# proximity.net
KiCad netlist of a schematic drawn in EAGLE
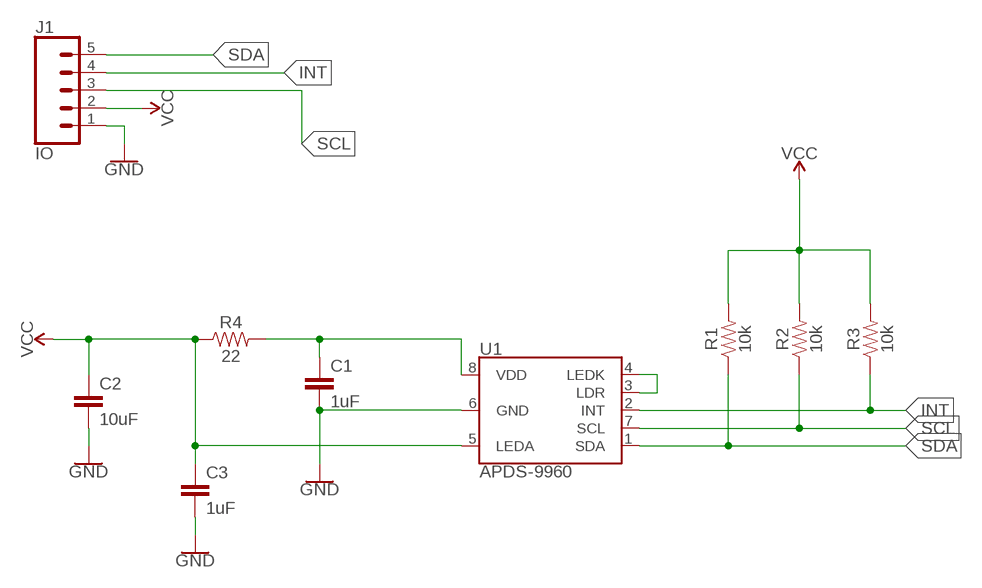
[diagram p0: schematic, sheet 1]

(export (version "E")
  (design (tool "Eeschema 10.0.6"))
  (components
    (comp (ref "C1")
      (value "1uF")
      (footprint "eagle-import:CAP-PTH-SMALL-KIT")
      (libsource (lib "eagle-import") (part "0.1UF-KIT-EZ-50V-20%"))
    )
    (comp (ref "C2")
      (value "10uF")
      (footprint "eagle-import:CAP-PTH-SMALL-KIT")
      (libsource (lib "eagle-import") (part "0.1UF-KIT-EZ-50V-20%"))
    )
    (comp (ref "C3")
      (value "1uF")
      (footprint "eagle-import:CAP-PTH-SMALL-KIT")
      (libsource (lib "eagle-import") (part "0.1UF-KIT-EZ-50V-20%"))
    )
    (comp (ref "J1")
      (value "IO")
      (footprint "eagle-import:1X05")
      (libsource (lib "eagle-import") (part "CONN_05"))
    )
    (comp (ref "R1")
      (value "10k")
      (footprint "eagle-import:AXIAL-0.3")
      (libsource (lib "eagle-import") (part "10KOHM-HORIZ-1/4W-1%"))
    )
    (comp (ref "R2")
      (value "10k")
      (footprint "eagle-import:AXIAL-0.3")
      (libsource (lib "eagle-import") (part "10KOHM-HORIZ-1/4W-1%"))
    )
    (comp (ref "R3")
      (value "10k")
      (footprint "eagle-import:AXIAL-0.3")
      (libsource (lib "eagle-import") (part "10KOHM-HORIZ-1/4W-1%"))
    )
    (comp (ref "R4")
      (value "22")
      (footprint "eagle-import:AXIAL-0.3")
      (libsource (lib "eagle-import") (part "10KOHM-HORIZ-1/4W-1%"))
    )
    (comp (ref "U1")
      (value "APDS-9960")
      (footprint "eagle-import:APDS-9960")
      (libsource (lib "eagle-import") (part "APDS-9960"))
    )
  )
  (nets
    (net (code "1") (name "GND") (class "Default")
      (node (ref "C1") (pin "2") (pinfunction "2_2") (pintype "passive"))
      (node (ref "C2") (pin "2") (pinfunction "2_2") (pintype "passive"))
      (node (ref "C3") (pin "2") (pinfunction "2_2") (pintype "passive"))
      (node (ref "J1") (pin "1") (pinfunction "1_1") (pintype "passive"))
      (node (ref "U1") (pin "6") (pinfunction "GND_6") (pintype "bidirectional"))
    )
    (net (code "2") (name "INT") (class "Default")
      (node (ref "J1") (pin "4") (pinfunction "4_4") (pintype "passive"))
      (node (ref "R3") (pin "P$1") (pinfunction "1_P$1") (pintype "passive"))
      (node (ref "U1") (pin "2") (pinfunction "INT_2") (pintype "bidirectional"))
    )
    (net (code "3") (name "Net-(R4-2)") (class "Default")
      (node (ref "C1") (pin "1") (pinfunction "1_1") (pintype "passive"))
      (node (ref "R4") (pin "P$2") (pinfunction "2_P$2") (pintype "passive"))
      (node (ref "U1") (pin "8") (pinfunction "VDD_8") (pintype "bidirectional"))
    )
    (net (code "4") (name "Net-(U1-LDR)") (class "Default")
      (node (ref "U1") (pin "3") (pinfunction "LDR_3") (pintype "bidirectional"))
      (node (ref "U1") (pin "4") (pinfunction "LEDK_4") (pintype "bidirectional"))
    )
    (net (code "5") (name "SCL") (class "Default")
      (node (ref "J1") (pin "3") (pinfunction "3_3") (pintype "passive"))
      (node (ref "R2") (pin "P$1") (pinfunction "1_P$1") (pintype "passive"))
      (node (ref "U1") (pin "7") (pinfunction "SCL_7") (pintype "bidirectional"))
    )
    (net (code "6") (name "SDA") (class "Default")
      (node (ref "J1") (pin "5") (pinfunction "5_5") (pintype "passive"))
      (node (ref "R1") (pin "P$1") (pinfunction "1_P$1") (pintype "passive"))
      (node (ref "U1") (pin "1") (pinfunction "SDA_1") (pintype "bidirectional"))
    )
    (net (code "7") (name "VCC") (class "Default")
      (node (ref "C2") (pin "1") (pinfunction "1_1") (pintype "passive"))
      (node (ref "C3") (pin "1") (pinfunction "1_1") (pintype "passive"))
      (node (ref "J1") (pin "2") (pinfunction "2_2") (pintype "passive"))
      (node (ref "R1") (pin "P$2") (pinfunction "2_P$2") (pintype "passive"))
      (node (ref "R2") (pin "P$2") (pinfunction "2_P$2") (pintype "passive"))
      (node (ref "R3") (pin "P$2") (pinfunction "2_P$2") (pintype "passive"))
      (node (ref "R4") (pin "P$1") (pinfunction "1_P$1") (pintype "passive"))
      (node (ref "U1") (pin "5") (pinfunction "LEDA_5") (pintype "bidirectional"))
    )
  )
)
